# UART.net
KiCad netlist of a schematic drawn in Altium Designer
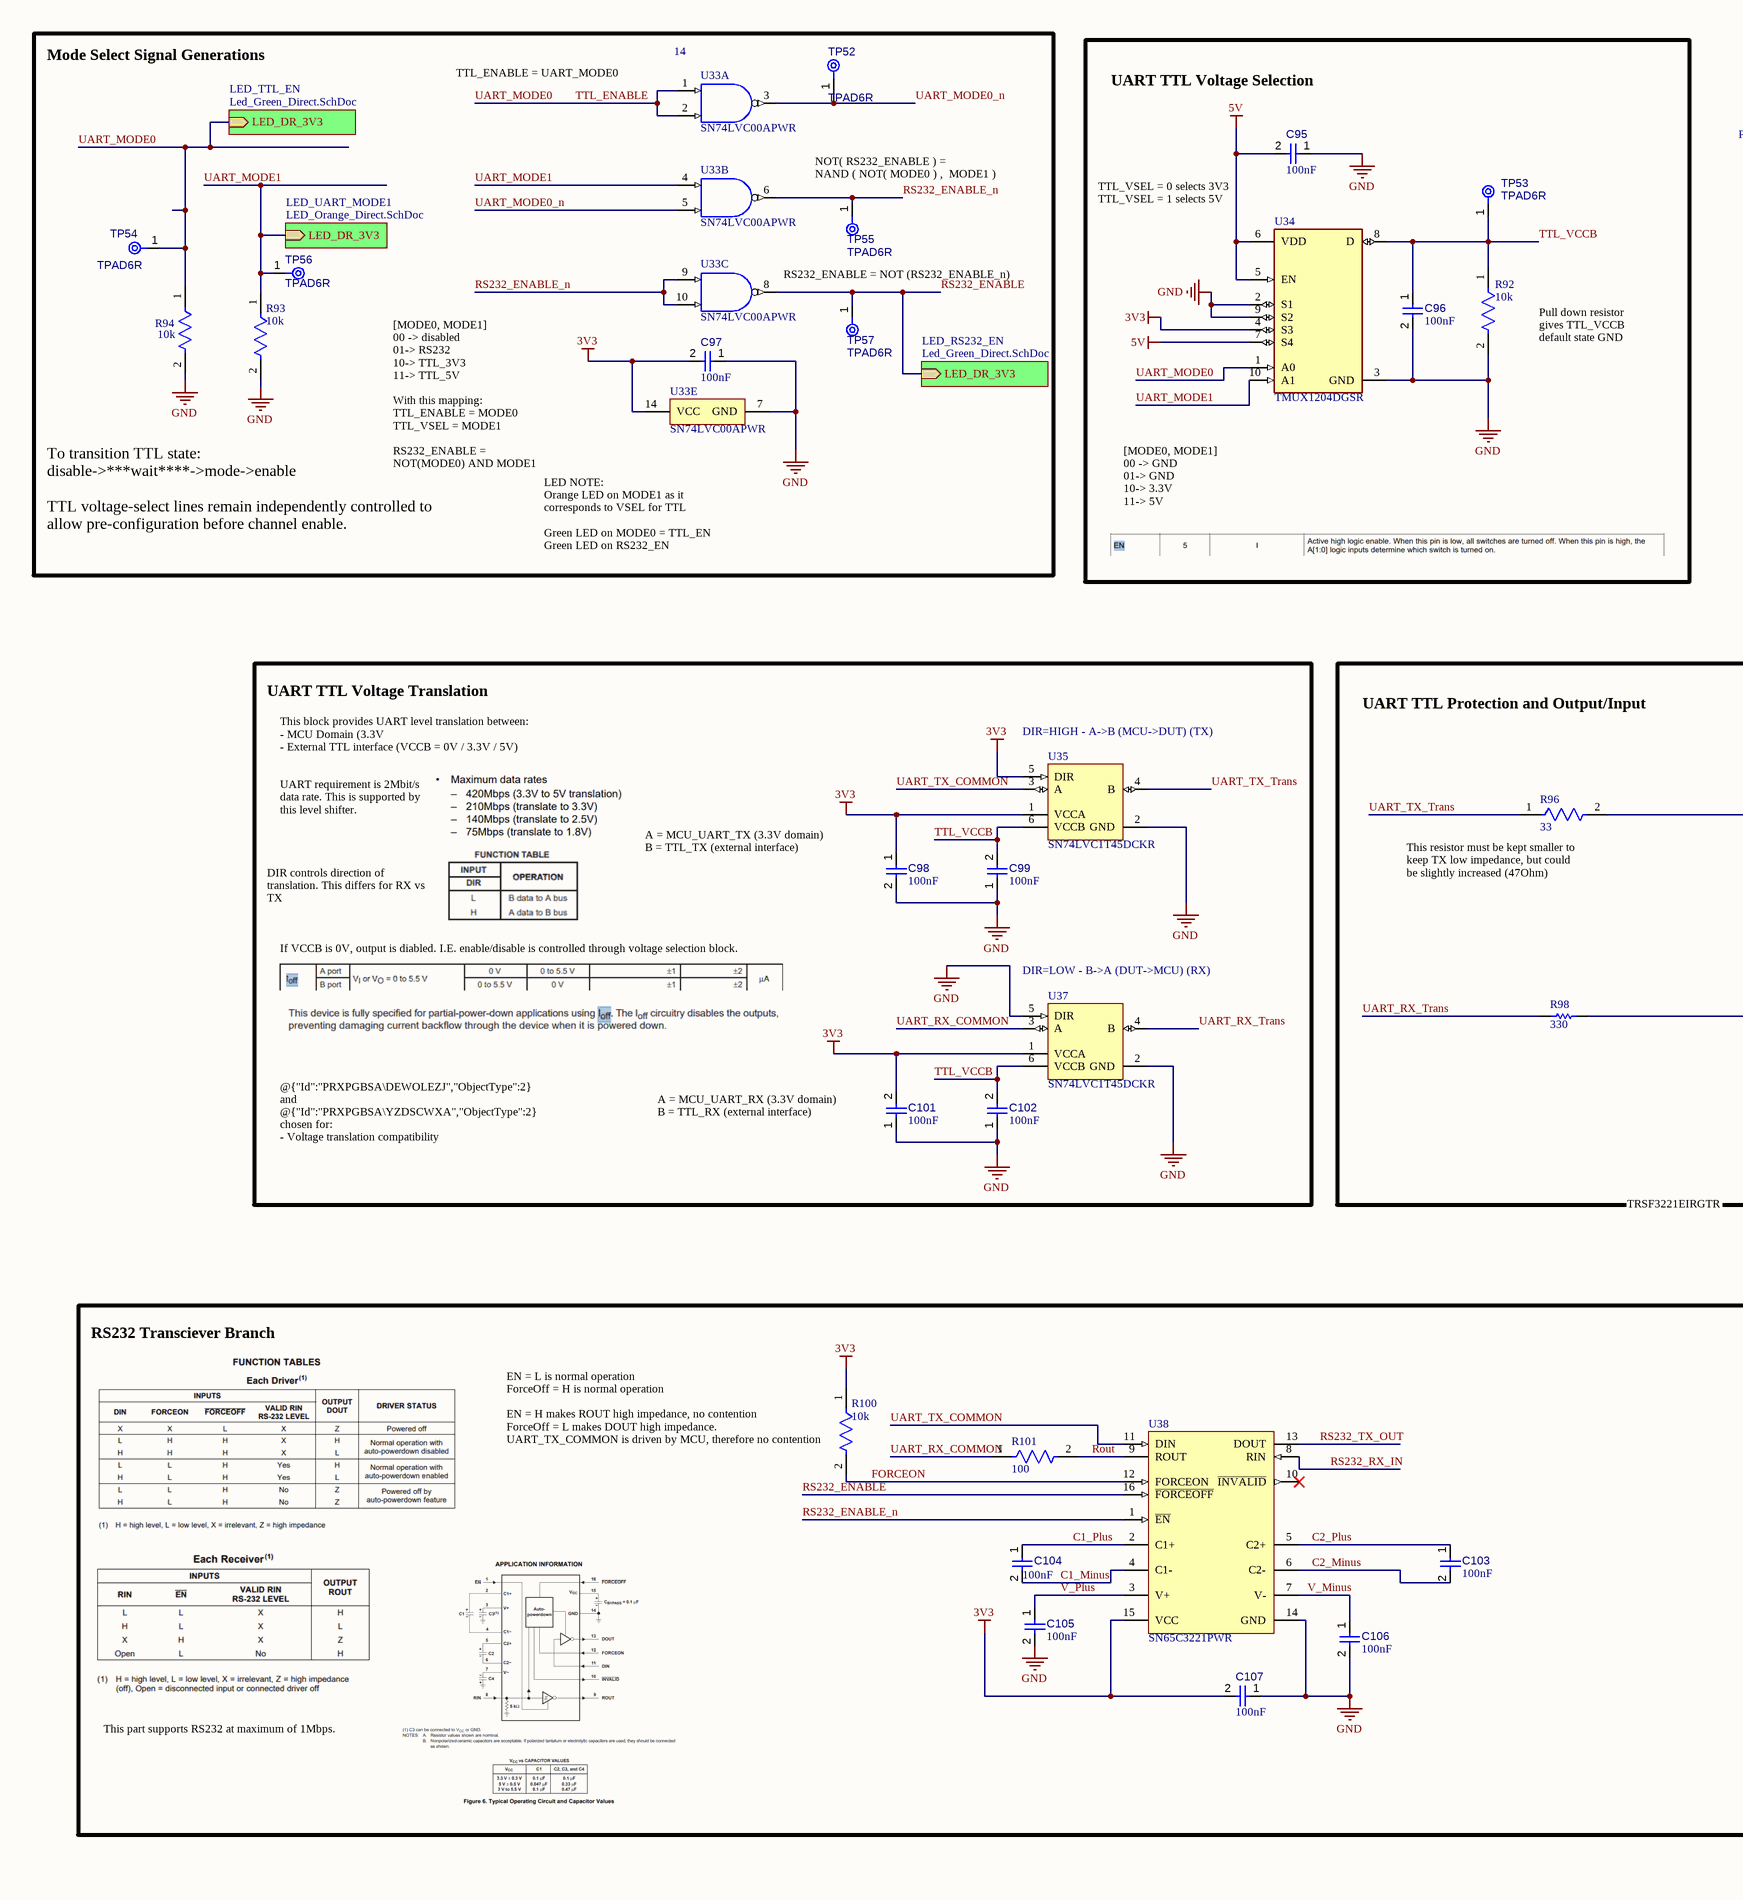
[diagram p0:  UART.SchDoc, left]
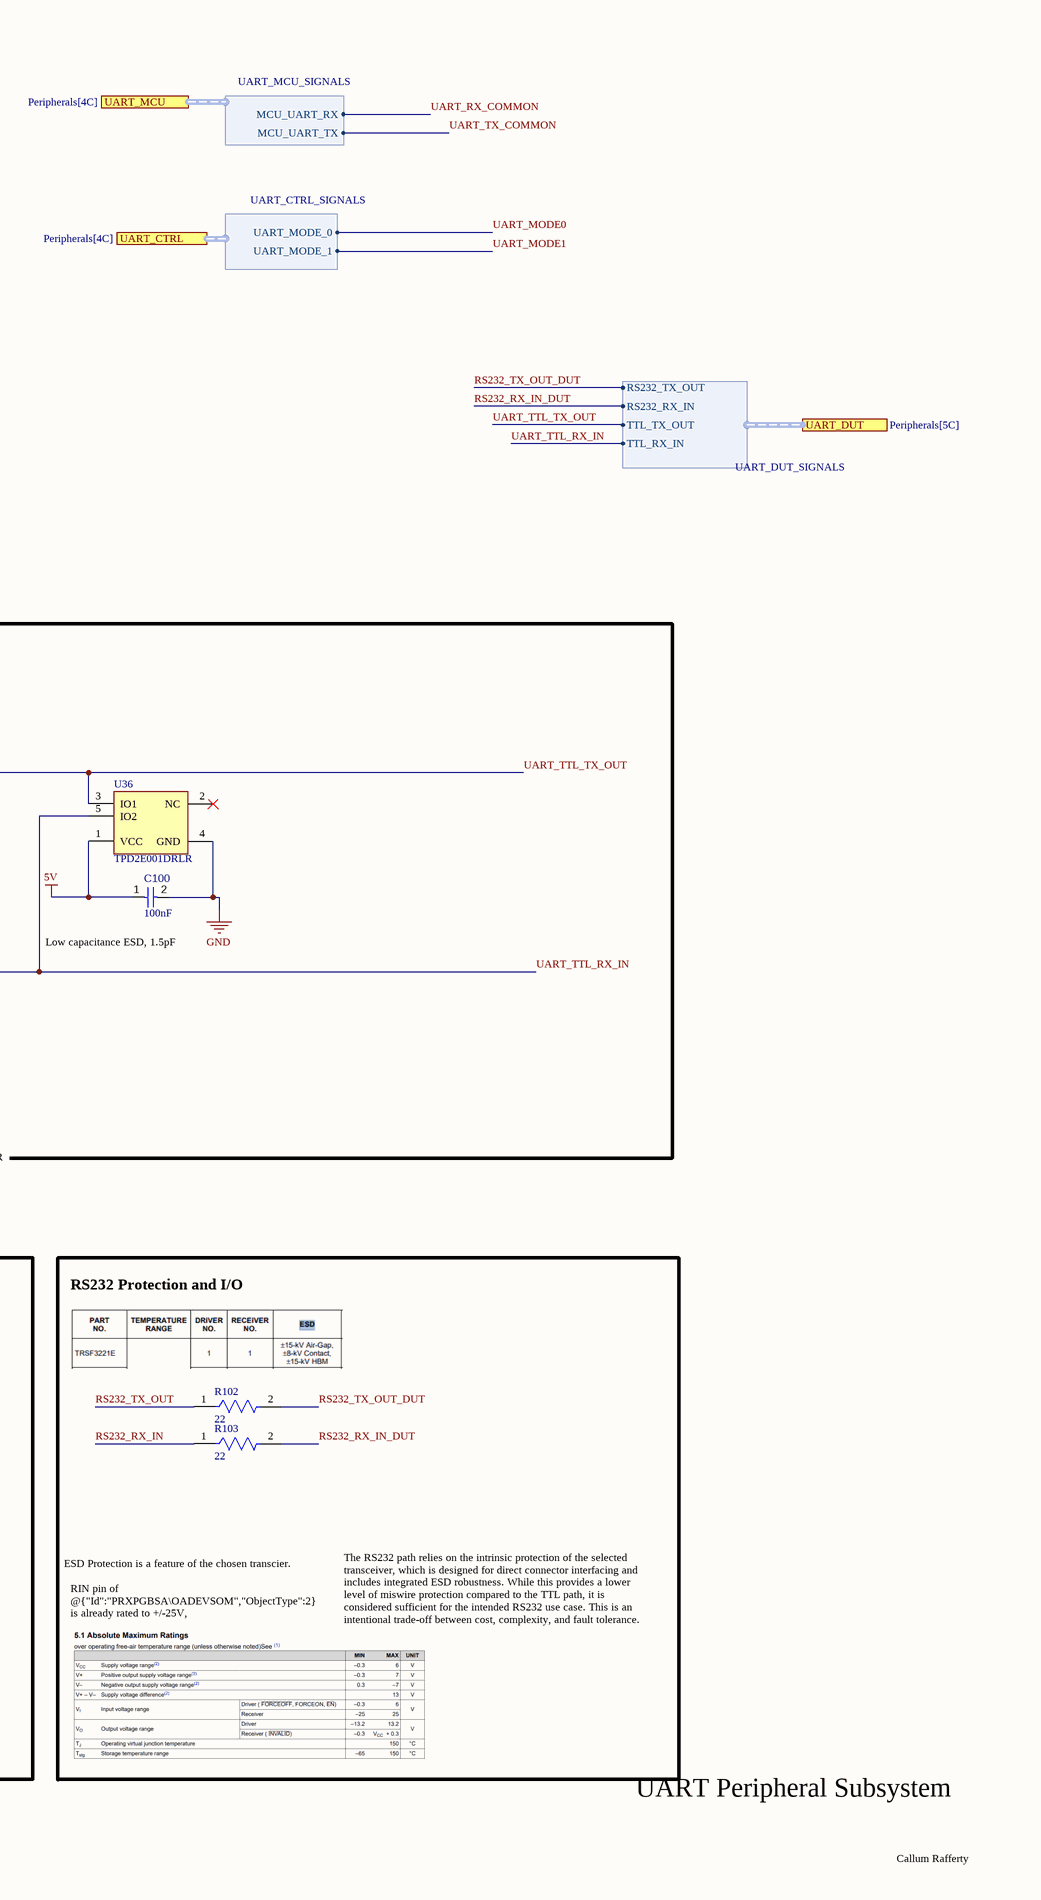
[diagram p1:  UART.SchDoc, right]

(export (version "E")
  (design (tool "Eeschema 10.0.6"))
  (components
    (comp (ref "C95")
      (value "100nF")
      (footprint "CAPC1608X90X40NL10T20")
      (description "Chip Capacitor, 100 nF, +/- 10%, 50 V, 0603 (1608 Metric)")
      (fields (field (name "TOLERANCE") "10%") (field (name "Comment") "Capacitor 100 nF +/-10% 50 V 0603"))
      (libsource (lib "HIL RIG FYP") (part "CAP-NP-2"))
    )
    (comp (ref "C96")
      (value "100nF")
      (footprint "CAPC1608X90X40NL10T20")
      (description "Chip Capacitor, 100 nF, +/- 10%, 50 V, 0603 (1608 Metric)")
      (fields (field (name "TOLERANCE") "10%") (field (name "Comment") "Capacitor 100 nF +/-10% 50 V 0603"))
      (libsource (lib "HIL RIG FYP") (part "CAP-NP-2"))
    )
    (comp (ref "C97")
      (value "100nF")
      (footprint "CAPC1608X90X40NL10T20")
      (description "Chip Capacitor, 100 nF, +/- 10%, 50 V, 0603 (1608 Metric)")
      (fields (field (name "TOLERANCE") "10%") (field (name "Comment") "Capacitor 100 nF +/-10% 50 V 0603"))
      (libsource (lib "HIL RIG FYP") (part "CAP-NP-2"))
    )
    (comp (ref "C98")
      (value "100nF")
      (footprint "CAPC1608X90X40NL10T20")
      (description "Chip Capacitor, 100 nF, +/- 10%, 50 V, 0603 (1608 Metric)")
      (fields (field (name "TOLERANCE") "10%") (field (name "Comment") "Capacitor 100 nF +/-10% 50 V 0603"))
      (libsource (lib "HIL RIG FYP") (part "CAP-NP-2"))
    )
    (comp (ref "C99")
      (value "100nF")
      (footprint "CAPC1608X90X40NL10T20")
      (description "Chip Capacitor, 100 nF, +/- 10%, 50 V, 0603 (1608 Metric)")
      (fields (field (name "TOLERANCE") "10%") (field (name "Comment") "Capacitor 100 nF +/-10% 50 V 0603"))
      (libsource (lib "HIL RIG FYP") (part "CAP-NP-2"))
    )
    (comp (ref "C100")
      (value "100nF")
      (footprint "CAPC1608X90X40NL10T20")
      (description "Chip Capacitor, 100 nF, +/- 10%, 50 V, 0603 (1608 Metric)")
      (fields (field (name "TOLERANCE") "10%") (field (name "Comment") "Capacitor 100 nF +/-10% 50 V 0603"))
      (libsource (lib "HIL RIG FYP") (part "CAP-NP-2"))
    )
    (comp (ref "C101")
      (value "100nF")
      (footprint "CAPC1608X90X40NL10T20")
      (description "Chip Capacitor, 100 nF, +/- 10%, 50 V, 0603 (1608 Metric)")
      (fields (field (name "TOLERANCE") "10%") (field (name "Comment") "Capacitor 100 nF +/-10% 50 V 0603"))
      (libsource (lib "HIL RIG FYP") (part "CAP-NP-2"))
    )
    (comp (ref "C102")
      (value "100nF")
      (footprint "CAPC1608X90X40NL10T20")
      (description "Chip Capacitor, 100 nF, +/- 10%, 50 V, 0603 (1608 Metric)")
      (fields (field (name "TOLERANCE") "10%") (field (name "Comment") "Capacitor 100 nF +/-10% 50 V 0603"))
      (libsource (lib "HIL RIG FYP") (part "CAP-NP-2"))
    )
    (comp (ref "C103")
      (value "100nF")
      (footprint "CAPC1608X90X40LL10T20")
      (description "Chip Capacitor, 100 nF, +/- 10%, 50 V, 0603 (1608 Metric)")
      (fields (field (name "TOLERANCE") "10%") (field (name "Comment") "Capacitor 100 nF +/-10% 50 V 0603"))
      (libsource (lib "HIL RIG FYP") (part "CAP-NP-2"))
    )
    (comp (ref "C104")
      (value "100nF")
      (footprint "CAPC1608X90X40LL10T20")
      (description "Chip Capacitor, 100 nF, +/- 10%, 50 V, 0603 (1608 Metric)")
      (fields (field (name "TOLERANCE") "10%") (field (name "Comment") "Capacitor 100 nF +/-10% 50 V 0603"))
      (libsource (lib "HIL RIG FYP") (part "CAP-NP-2"))
    )
    (comp (ref "C105")
      (value "100nF")
      (footprint "CAPC1608X90X40LL10T20")
      (description "Chip Capacitor, 100 nF, +/- 10%, 50 V, 0603 (1608 Metric)")
      (fields (field (name "TOLERANCE") "10%") (field (name "Comment") "Capacitor 100 nF +/-10% 50 V 0603"))
      (libsource (lib "HIL RIG FYP") (part "CAP-NP-2"))
    )
    (comp (ref "C106")
      (value "100nF")
      (footprint "CAPC1608X90X40LL10T20")
      (description "Chip Capacitor, 100 nF, +/- 10%, 50 V, 0603 (1608 Metric)")
      (fields (field (name "TOLERANCE") "10%") (field (name "Comment") "Capacitor 100 nF +/-10% 50 V 0603"))
      (libsource (lib "HIL RIG FYP") (part "CAP-NP-2"))
    )
    (comp (ref "C107")
      (value "100nF")
      (footprint "CAPC1608X90X40NL10T20")
      (description "Chip Capacitor, 100 nF, +/- 10%, 50 V, 0603 (1608 Metric)")
      (fields (field (name "TOLERANCE") "10%") (field (name "Comment") "Capacitor 100 nF +/-10% 50 V 0603"))
      (libsource (lib "HIL RIG FYP") (part "CAP-NP-2"))
    )
    (comp (ref "R92")
      (value "10k")
      (footprint "FP-RT0603-IPC_C")
      (description "Res Thin Film 0603 10K Ohm 0.1% 1/10W ¦25ppm/¦C SMD Paper T/R")
      (fields (field (name "TOLERANCE") "0.1%") (field (name "Comment") "RT0603BRD0710KL"))
      (libsource (lib "HIL RIG FYP") (part "1029c3af85768c4190bb7ad29bc67b5"))
    )
    (comp (ref "R93")
      (value "10k")
      (footprint "FP-RT0603-IPC_C")
      (description "Res Thin Film 0603 10K Ohm 0.1% 1/10W ¦25ppm/¦C SMD Paper T/R")
      (fields (field (name "TOLERANCE") "0.1%") (field (name "Comment") "RT0603BRD0710KL"))
      (libsource (lib "HIL RIG FYP") (part "1029c3af85768c4190bb7ad29bc67b5"))
    )
    (comp (ref "R94")
      (value "10k")
      (footprint "FP-RT0603-IPC_C")
      (description "Res Thin Film 0603 10K Ohm 0.1% 1/10W ¦25ppm/¦C SMD Paper T/R")
      (fields (field (name "TOLERANCE") "0.1%") (field (name "Comment") "RT0603BRD0710KL"))
      (libsource (lib "HIL RIG FYP") (part "1029c3af85768c4190bb7ad29bc67b5"))
    )
    (comp (ref "R96")
      (value "33")
      (footprint "FP-AC0603-IPC_C")
      (description "Res Thick Film 0603 33 Ohm 1% 0.1W(1/10W) ±100ppm/C Pad SMD T/R Automotive AEC-Q200")
      (fields (field (name "TOLERANCE") "1%") (field (name "Comment") "AC0603FR-0733RL"))
      (libsource (lib "HIL RIG FYP") (part "1029c3af85768c4190bb7ad29bc67b5"))
    )
    (comp (ref "R98")
      (value "330")
      (footprint "RESC1608X55X25LL10T15")
      (description "Res Thick Film 0603 330 Ohm 5% 0.1W(1/10W) ±100ppm/C Epoxy SMD T/R")
      (fields (field (name "TOLERANCE") "5%") (field (name "Comment") "RC0603JR-07330RL"))
      (libsource (lib "HIL RIG FYP") (part "RES-2"))
    )
    (comp (ref "R100")
      (value "10k")
      (footprint "FP-RT0603-IPC_B")
      (description "Res Thin Film 0603 10K Ohm 0.1% 1/10W ¦25ppm/¦C SMD Paper T/R")
      (fields (field (name "TOLERANCE") "0.1%") (field (name "Comment") "RT0603BRD0710KL"))
      (libsource (lib "HIL RIG FYP") (part "1029c3af85768c4190bb7ad29bc67b5"))
    )
    (comp (ref "R101")
      (value "100")
      (footprint "FP-RT0603-IPC_B")
      (description "100mW Thin Film Resistor 75V ±25ppm/℃ ±0.1% 100Ω 0603 Chip Resistor - Surface Mount ROHS")
      (fields (field (name "TOLERANCE") "0.1%") (field (name "Comment") "RT0603BRD07100RL"))
      (libsource (lib "HIL RIG FYP") (part "1029c3af85768c4190bb7ad29bc67b5"))
    )
    (comp (ref "R102")
      (value "22")
      (footprint "FP-RC0603-0_55-IPC_A")
      (description "100mW Thick Film Resistors 75V ±100ppm/℃ ±5% 22Ω 0603 Chip Resistor - Surface Mount ROHS")
      (fields (field (name "TOLERANCE") "5%") (field (name "Comment") "RC0603JR-0722RL"))
      (libsource (lib "HIL RIG FYP") (part "1029c3af85768c4190bb7ad29bc67b5"))
    )
    (comp (ref "R103")
      (value "22")
      (footprint "FP-RC0603-0_55-IPC_A")
      (description "100mW Thick Film Resistors 75V ±100ppm/℃ ±5% 22Ω 0603 Chip Resistor - Surface Mount ROHS")
      (fields (field (name "TOLERANCE") "5%") (field (name "Comment") "RC0603JR-0722RL"))
      (libsource (lib "HIL RIG FYP") (part "1029c3af85768c4190bb7ad29bc67b5"))
    )
    (comp (ref "TP52")
      (value "TPAD6R")
      (footprint "TP06R")
      (description "0.6mm round")
      (libsource (lib "HIL RIG FYP") (part "CMP-001-0001-4"))
    )
    (comp (ref "TP53")
      (value "TPAD6R")
      (footprint "TP06R")
      (description "0.6mm round")
      (libsource (lib "HIL RIG FYP") (part "CMP-001-0001-4"))
    )
    (comp (ref "TP54")
      (value "TPAD6R")
      (footprint "TP06R")
      (description "0.6mm round")
      (libsource (lib "HIL RIG FYP") (part "CMP-001-0001-4"))
    )
    (comp (ref "TP55")
      (value "TPAD6R")
      (footprint "TP06R")
      (description "0.6mm round")
      (libsource (lib "HIL RIG FYP") (part "CMP-001-0001-4"))
    )
    (comp (ref "TP56")
      (value "TPAD6R")
      (footprint "TP06R")
      (description "0.6mm round")
      (libsource (lib "HIL RIG FYP") (part "CMP-001-0001-4"))
    )
    (comp (ref "TP57")
      (value "TPAD6R")
      (footprint "TP06R")
      (description "0.6mm round")
      (libsource (lib "HIL RIG FYP") (part "CMP-001-0001-4"))
    )
    (comp (ref "U33")
      (value "SN74LVC00APWR")
      (footprint "FP-PW0014A-IPC_B")
      (description "4.1NS@ 3.3V, 50PF 1 2 4 4 1.65V 3.6V 24MA Nand Gate Lvc 24MA TSSOP-14 , 1.2MM")
      (fields (field (name "PINS") "14"))
      (libsource (lib "HIL RIG FYP") (part "TI-NAND-4-2IN-14_G"))
    )
    (comp (ref "U34")
      (value "TMUX1204DGSR")
      (footprint "FP-DGS0010A-IPC_B")
      (description "5V, 4: 1, 1-channel, analog multiplexer, 1.8V compatible logic 10-VSSOP -40 to 125")
      (libsource (lib "HIL RIG FYP") (part "ab1b3b8b06dda84b0c8889944130d19"))
    )
    (comp (ref "U35")
      (value "SN74LVC1T45DCKR")
      (footprint "DCK0006A_M")
      (description "Translators, Level Shifters bidirectional 420Mbps 1.65V~5.5VCCA 1.65V~5.5VCCB")
      (libsource (lib "HIL RIG FYP") (part "TI-SN74XVC1T45-6"))
    )
    (comp (ref "U36")
      (value "TPD2E001DRLR")
      (footprint "DRL0005A_M")
      (description "11V Unidirectional 5.5V SOT-553-5 ESD and Surge Protection (TVS/ESD) ROHS")
      (libsource (lib "HIL RIG FYP") (part "TI-TPD2E001-SOT_DRL-5"))
    )
    (comp (ref "U37")
      (value "SN74LVC1T45DCKR")
      (footprint "DCK0006A_M")
      (description "Translators, Level Shifters bidirectional 420Mbps 1.65V~5.5VCCA 1.65V~5.5VCCB")
      (libsource (lib "HIL RIG FYP") (part "TI-SN74XVC1T45-6"))
    )
    (comp (ref "U38")
      (value "SN65C3221PWR")
      (footprint "PW0016A_L")
      (libsource (lib "HIL RIG FYP") (part "TI-SN65C3221-TSSOP_PW-16"))
    )
  )
  (nets
    (net (code "4") (name "/C1_Minus") (class "Default")
      (node (ref "C104") (pin "2") (pinfunction "2_2") (pintype "passive"))
      (node (ref "U38") (pin "4") (pinfunction "C1-_4") (pintype "passive"))
    )
    (net (code "5") (name "/C1_Plus") (class "Default")
      (node (ref "C104") (pin "1") (pinfunction "1_1") (pintype "passive"))
      (node (ref "U38") (pin "2") (pinfunction "C1+_2") (pintype "passive"))
    )
    (net (code "6") (name "/C2_Minus") (class "Default")
      (node (ref "C103") (pin "2") (pinfunction "2_2") (pintype "passive"))
      (node (ref "U38") (pin "6") (pinfunction "C2-_6") (pintype "passive"))
    )
    (net (code "7") (name "/C2_Plus") (class "Default")
      (node (ref "C103") (pin "1") (pinfunction "1_1") (pintype "passive"))
      (node (ref "U38") (pin "5") (pinfunction "C2+_5") (pintype "passive"))
    )
    (net (code "8") (name "/FORCEON") (class "Default")
      (node (ref "R100") (pin "2") (pinfunction "2_2") (pintype "passive"))
      (node (ref "U38") (pin "12") (pinfunction "FORCEON_12") (pintype "input"))
    )
    (net (code "9") (name "/RS232_ENABLE") (class "Default")
      (node (ref "TP57") (pin "1") (pinfunction "TP_1") (pintype "passive"))
      (node (ref "U33") (pin "8") (pinfunction "3Y_8") (pintype "output"))
      (node (ref "U38") (pin "16") (pinfunction "~{FORCEOFF}_16") (pintype "input"))
    )
    (net (code "10") (name "/RS232_ENABLE_n") (class "Default")
      (node (ref "TP55") (pin "1") (pinfunction "TP_1") (pintype "passive"))
      (node (ref "U33") (pin "10") (pinfunction "3B_10") (pintype "input"))
      (node (ref "U33") (pin "6") (pinfunction "2Y_6") (pintype "output"))
      (node (ref "U33") (pin "9") (pinfunction "3A_9") (pintype "input"))
      (node (ref "U38") (pin "1") (pinfunction "~{EN}_1") (pintype "input"))
    )
    (net (code "11") (name "/RS232_RX_IN") (class "Default")
      (node (ref "R103") (pin "1") (pinfunction "1_1") (pintype "passive"))
      (node (ref "U38") (pin "8") (pinfunction "RIN_8") (pintype "input"))
    )
    (net (code "12") (name "/RS232_RX_IN_DUT") (class "Default")
      (node (ref "R103") (pin "2") (pinfunction "2_2") (pintype "passive"))
    )
    (net (code "13") (name "/RS232_TX_OUT") (class "Default")
      (node (ref "R102") (pin "1") (pinfunction "1_1") (pintype "passive"))
      (node (ref "U38") (pin "13") (pinfunction "DOUT_13") (pintype "tri_state"))
    )
    (net (code "14") (name "/RS232_TX_OUT_DUT") (class "Default")
      (node (ref "R102") (pin "2") (pinfunction "2_2") (pintype "passive"))
    )
    (net (code "15") (name "/Rout") (class "Default")
      (node (ref "R101") (pin "2") (pinfunction "2_2") (pintype "passive"))
      (node (ref "U38") (pin "9") (pinfunction "ROUT_9") (pintype "tri_state"))
    )
    (net (code "16") (name "/TTL_ENABLE") (class "Default")
      (node (ref "R94") (pin "1") (pinfunction "1_1") (pintype "passive"))
      (node (ref "TP54") (pin "1") (pinfunction "TP_1") (pintype "passive"))
      (node (ref "U33") (pin "1") (pinfunction "1A_1") (pintype "input"))
      (node (ref "U33") (pin "2") (pinfunction "1B_2") (pintype "input"))
      (node (ref "U34") (pin "1") (pinfunction "A0_1") (pintype "input"))
    )
    (net (code "17") (name "/TTL_VCCB") (class "Default")
      (node (ref "C102") (pin "2") (pinfunction "2_2") (pintype "passive"))
      (node (ref "C96") (pin "1") (pinfunction "1_1") (pintype "passive"))
      (node (ref "C99") (pin "2") (pinfunction "2_2") (pintype "passive"))
      (node (ref "R92") (pin "1") (pinfunction "1_1") (pintype "passive"))
      (node (ref "TP53") (pin "1") (pinfunction "TP_1") (pintype "passive"))
      (node (ref "U34") (pin "8") (pinfunction "D_8") (pintype "bidirectional"))
      (node (ref "U35") (pin "6") (pinfunction "VCCB_6") (pintype "power_in"))
      (node (ref "U37") (pin "6") (pinfunction "VCCB_6") (pintype "power_in"))
    )
    (net (code "18") (name "/UART_MODE0_n") (class "Default")
      (node (ref "TP52") (pin "1") (pinfunction "TP_1") (pintype "passive"))
      (node (ref "U33") (pin "3") (pinfunction "1Y_3") (pintype "output"))
      (node (ref "U33") (pin "5") (pinfunction "2B_5") (pintype "input"))
    )
    (net (code "19") (name "/UART_MODE1") (class "Default")
      (node (ref "R93") (pin "1") (pinfunction "1_1") (pintype "passive"))
      (node (ref "TP56") (pin "1") (pinfunction "TP_1") (pintype "passive"))
      (node (ref "U33") (pin "4") (pinfunction "2A_4") (pintype "input"))
      (node (ref "U34") (pin "10") (pinfunction "A1_10") (pintype "input"))
    )
    (net (code "20") (name "/UART_RX_COMMON") (class "Default")
      (node (ref "R101") (pin "1") (pinfunction "1_1") (pintype "passive"))
      (node (ref "U37") (pin "3") (pinfunction "A_3") (pintype "bidirectional"))
    )
    (net (code "21") (name "/UART_RX_Trans") (class "Default")
      (node (ref "R98") (pin "1") (pinfunction "1_1") (pintype "passive"))
      (node (ref "U37") (pin "4") (pinfunction "B_4") (pintype "bidirectional"))
    )
    (net (code "22") (name "/UART_TTL_RX_IN") (class "Default")
      (node (ref "R98") (pin "2") (pinfunction "2_2") (pintype "passive"))
      (node (ref "U36") (pin "5") (pinfunction "IO2_5") (pintype "passive"))
    )
    (net (code "23") (name "/UART_TTL_TX_OUT") (class "Default")
      (node (ref "R96") (pin "2") (pinfunction "2_2") (pintype "passive"))
      (node (ref "U36") (pin "3") (pinfunction "IO1_3") (pintype "passive"))
    )
    (net (code "24") (name "/UART_TX_COMMON") (class "Default")
      (node (ref "U35") (pin "3") (pinfunction "A_3") (pintype "bidirectional"))
      (node (ref "U38") (pin "11") (pinfunction "DIN_11") (pintype "input"))
    )
    (net (code "25") (name "/UART_TX_Trans") (class "Default")
      (node (ref "R96") (pin "1") (pinfunction "1_1") (pintype "passive"))
      (node (ref "U35") (pin "4") (pinfunction "B_4") (pintype "bidirectional"))
    )
    (net (code "26") (name "/V_Minus") (class "Default")
      (node (ref "C106") (pin "1") (pinfunction "1_1") (pintype "passive"))
      (node (ref "U38") (pin "7") (pinfunction "V-_7") (pintype "power_in"))
    )
    (net (code "27") (name "/V_Plus") (class "Default")
      (node (ref "C105") (pin "1") (pinfunction "1_1") (pintype "passive"))
      (node (ref "U38") (pin "3") (pinfunction "V+_3") (pintype "power_in"))
    )
    (net (code "31") (name "3V3") (class "Default")
      (node (ref "C101") (pin "2") (pinfunction "2_2") (pintype "passive"))
      (node (ref "C107") (pin "2") (pinfunction "2_2") (pintype "passive"))
      (node (ref "C97") (pin "2") (pinfunction "2_2") (pintype "passive"))
      (node (ref "C98") (pin "1") (pinfunction "1_1") (pintype "passive"))
      (node (ref "R100") (pin "1") (pinfunction "1_1") (pintype "passive"))
      (node (ref "U33") (pin "14") (pinfunction "VCC_14") (pintype "power_in"))
      (node (ref "U34") (pin "4") (pinfunction "S3_4") (pintype "bidirectional"))
      (node (ref "U35") (pin "1") (pinfunction "VCCA_1") (pintype "power_in"))
      (node (ref "U35") (pin "5") (pinfunction "DIR_5") (pintype "input"))
      (node (ref "U37") (pin "1") (pinfunction "VCCA_1") (pintype "power_in"))
      (node (ref "U38") (pin "15") (pinfunction "VCC_15") (pintype "power_in"))
    )
    (net (code "32") (name "5V") (class "Default")
      (node (ref "C100") (pin "1") (pinfunction "1_1") (pintype "passive"))
      (node (ref "C95") (pin "2") (pinfunction "2_2") (pintype "passive"))
      (node (ref "U34") (pin "5") (pinfunction "EN_5") (pintype "input"))
      (node (ref "U34") (pin "6") (pinfunction "VDD_6") (pintype "power_in"))
      (node (ref "U34") (pin "7") (pinfunction "S4_7") (pintype "bidirectional"))
      (node (ref "U36") (pin "1") (pinfunction "VCC_1") (pintype "power_in"))
    )
    (net (code "33") (name "GND") (class "Default")
      (node (ref "C100") (pin "2") (pinfunction "2_2") (pintype "passive"))
      (node (ref "C101") (pin "1") (pinfunction "1_1") (pintype "passive"))
      (node (ref "C102") (pin "1") (pinfunction "1_1") (pintype "passive"))
      (node (ref "C105") (pin "2") (pinfunction "2_2") (pintype "passive"))
      (node (ref "C106") (pin "2") (pinfunction "2_2") (pintype "passive"))
      (node (ref "C107") (pin "1") (pinfunction "1_1") (pintype "passive"))
      (node (ref "C95") (pin "1") (pinfunction "1_1") (pintype "passive"))
      (node (ref "C96") (pin "2") (pinfunction "2_2") (pintype "passive"))
      (node (ref "C97") (pin "1") (pinfunction "1_1") (pintype "passive"))
      (node (ref "C98") (pin "2") (pinfunction "2_2") (pintype "passive"))
      (node (ref "C99") (pin "1") (pinfunction "1_1") (pintype "passive"))
      (node (ref "R92") (pin "2") (pinfunction "2_2") (pintype "passive"))
      (node (ref "R93") (pin "2") (pinfunction "2_2") (pintype "passive"))
      (node (ref "R94") (pin "2") (pinfunction "2_2") (pintype "passive"))
      (node (ref "U33") (pin "7") (pinfunction "GND_7") (pintype "power_in"))
      (node (ref "U34") (pin "2") (pinfunction "S1_2") (pintype "bidirectional"))
      (node (ref "U34") (pin "3") (pinfunction "GND_3") (pintype "power_in"))
      (node (ref "U34") (pin "9") (pinfunction "S2_9") (pintype "bidirectional"))
      (node (ref "U35") (pin "2") (pinfunction "GND_2") (pintype "power_in"))
      (node (ref "U36") (pin "4") (pinfunction "GND_4") (pintype "power_in"))
      (node (ref "U37") (pin "2") (pinfunction "GND_2") (pintype "power_in"))
      (node (ref "U37") (pin "5") (pinfunction "DIR_5") (pintype "input"))
      (node (ref "U38") (pin "14") (pinfunction "GND_14") (pintype "power_in"))
    )
    (net (code "34") (name "unconnected-(U36-NC-Pad2)") (class "Default")
      (node (ref "U36") (pin "2") (pinfunction "NC_2") (pintype "passive+no_connect"))
    )
    (net (code "35") (name "unconnected-(U38-~{INVALID}-Pad10)") (class "Default")
      (node (ref "U38") (pin "10") (pinfunction "~{INVALID}_10") (pintype "output+no_connect"))
    )
  )
)
